# uINS.net
KiCad netlist of a schematic drawn in Altium Designer
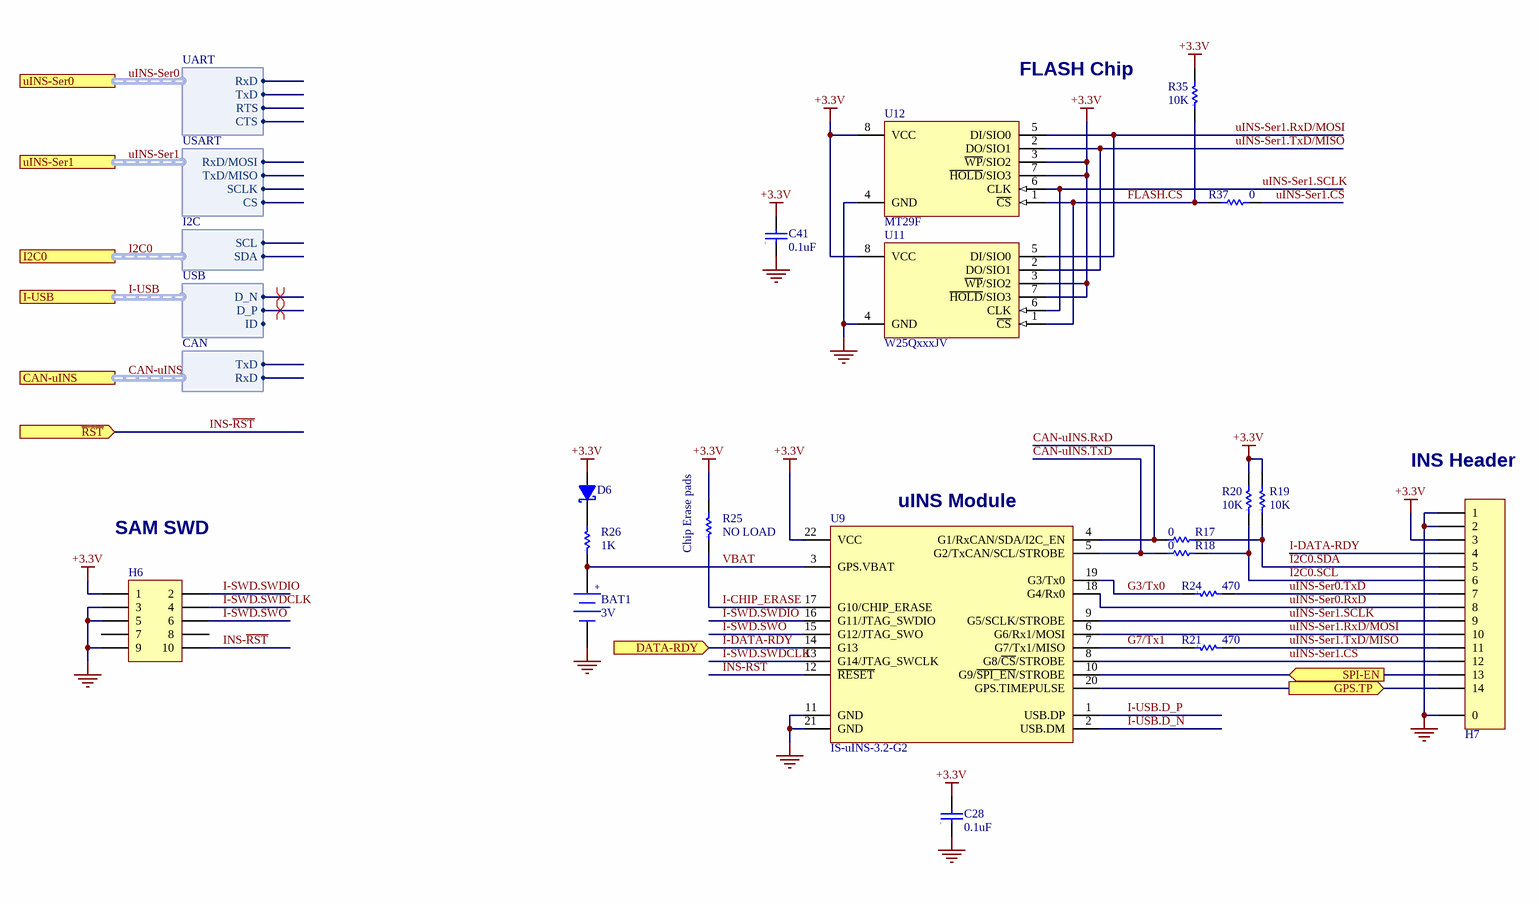
[diagram p0: uINS.SchDoc]

(export (version "E")
  (design (tool "Eeschema 10.0.6"))
  (components
    (comp (ref "BAT1")
      (value "Battery")
      (footprint "ML614S")
      (description "BATTERY LITH 3V RECHARGE SMD")
      (fields
        (field (name "MANUFACTURER") "Seiko")
        (field (name "MANUFACTURER PART NUMBER") "MS621T-FL11E")
        (field (name "VOLTAGE RATING") "3V")
      )
      (libsource (lib "General") (part "Battery"))
    )
    (comp (ref "C28")
      (value "0.1uF")
      (footprint "0402")
      (description "CAP CER .10UF 50V X7R 10% 0402")
      (fields
        (field (name "MANUFACTURER") "TDK Corporation")
        (field (name "MANUFACTURER PART NUMBER") "C1005X7R1H104K")
        (field (name "PUBLISHER") "Altium Limited")
      )
      (libsource (lib "General") (part "Cap"))
    )
    (comp (ref "C41")
      (value "0.1uF")
      (footprint "0402")
      (description "CAP CER .10UF 50V X7R 10% 0402")
      (fields
        (field (name "MANUFACTURER") "TDK Corporation")
        (field (name "MANUFACTURER PART NUMBER") "C1005X7R1H104K")
        (field (name "PUBLISHER") "Altium Limited")
      )
      (libsource (lib "General") (part "Cap"))
    )
    (comp (ref "D6")
      (value "Diode - Schottky")
      (footprint "D0603B")
      (description "DIODE SCHOTTKY 30V 2A 0603")
      (fields
        (field (name "MANUFACTURER") "Vishay")
        (field (name "MANUFACTURER PART NUMBER") "VSKY20301608-G4-08")
      )
      (libsource (lib "General") (part "Diode - Schottky"))
    )
    (comp (ref "H6")
      (value "Hdr - 5x2pin")
      (footprint "FTSH-105-01-L-DV-K-A-P")
      (description "CONN HEADER 10POS DUAL .05\" SMD")
      (fields
        (field (name "MANUFACTURER") "Samtec")
        (field (name "MANUFACTURER PART NUMBER") "FTSH-105-01-L-DV-K-A-P")
      )
      (libsource (lib "Connectors") (part "Hdr - 5x2pin"))
    )
    (comp (ref "H7")
      (value "Hdr - 14pin - mount")
      (footprint "SM14B-GHS-TB(LF)(SN)")
      (description "CONN HEADER GH SIDE 14POS 1.25MM")
      (fields
        (field (name "MANUFACTURER") "JST")
        (field (name "MANUFACTURER PART NUMBER") "SM14B-GHS-TB(LF)(SN)")
      )
      (libsource (lib "Connectors") (part "Hdr - 14pin - mount"))
    )
    (comp (ref "R17")
      (value "0")
      (footprint "R0402")
      (description "RES SMD 0 OHM JUMPER 1/16W 0402")
      (fields
        (field (name "MANUFACTURER") "Yageo")
        (field (name "MANUFACTURER PART NUMBER") "RC0402JR-070RL")
      )
      (libsource (lib "General") (part "Res"))
    )
    (comp (ref "R18")
      (value "0")
      (footprint "R0402")
      (description "RES SMD 0 OHM JUMPER 1/16W 0402")
      (fields
        (field (name "MANUFACTURER") "Yageo")
        (field (name "MANUFACTURER PART NUMBER") "RC0402JR-070RL")
      )
      (libsource (lib "General") (part "Res"))
    )
    (comp (ref "R19")
      (value "10K")
      (footprint "R0402")
      (description "RES 10K OHM 1/16W 1% 0402 SMD")
      (fields
        (field (name "MANUFACTURER") "Panasonic")
        (field (name "MANUFACTURER PART NUMBER") "ERJ-2RKF1002X")
      )
      (libsource (lib "") (part "Res_1"))
    )
    (comp (ref "R20")
      (value "10K")
      (footprint "R0402")
      (description "RES 10K OHM 1/16W 1% 0402 SMD")
      (fields
        (field (name "MANUFACTURER") "Panasonic")
        (field (name "MANUFACTURER PART NUMBER") "ERJ-2RKF1002X")
      )
      (libsource (lib "") (part "Res_1"))
    )
    (comp (ref "R21")
      (value "470")
      (footprint "R0402")
      (description "RES 470 OHM 1/16W 1% 0402 SMD")
      (fields
        (field (name "MANUFACTURER") "Vishay Dale")
        (field (name "MANUFACTURER PART NUMBER") "CRCW0402470RFKED")
      )
      (libsource (lib "") (part "Res_2"))
    )
    (comp (ref "R24")
      (value "470")
      (footprint "R0402")
      (description "RES 470 OHM 1/16W 1% 0402 SMD")
      (fields
        (field (name "MANUFACTURER") "Vishay Dale")
        (field (name "MANUFACTURER PART NUMBER") "CRCW0402470RFKED")
      )
      (libsource (lib "") (part "Res_2"))
    )
    (comp (ref "R25")
      (value "NO LOAD")
      (footprint "R0402")
      (description "RES 1.00K OHM 1/16W 1% 0402 SMD")
      (fields (field (name "Comment") "Res"))
      (libsource (lib "") (part "Res_1"))
    )
    (comp (ref "R26")
      (value "1K")
      (footprint "R0402")
      (description "RES 1.00K OHM 1/16W 1% 0402 SMD")
      (fields
        (field (name "MANUFACTURER") "Yageo")
        (field (name "MANUFACTURER PART NUMBER") "RC0402FR-071KL")
      )
      (libsource (lib "") (part "Res_1"))
    )
    (comp (ref "R35")
      (value "10K")
      (footprint "R0402")
      (description "RES 10K OHM 1/16W 1% 0402 SMD")
      (fields
        (field (name "MANUFACTURER") "Panasonic")
        (field (name "MANUFACTURER PART NUMBER") "ERJ-2RKF1002X")
      )
      (libsource (lib "") (part "Res_1"))
    )
    (comp (ref "R37")
      (value "0")
      (footprint "R0402")
      (description "RES SMD 0 OHM JUMPER 1/16W 0402")
      (fields
        (field (name "MANUFACTURER") "Yageo")
        (field (name "MANUFACTURER PART NUMBER") "RC0402JR-070RL")
      )
      (libsource (lib "General") (part "Res"))
    )
    (comp (ref "U9")
      (value "uINS")
      (footprint "IS-uINS-3.2_no_paste")
      (description "Inertial Sense uINS")
      (fields
        (field (name "MANUFACTURER") "Inertial Sense")
        (field (name "MANUFACTURER PART NUMBER") "IS-uINS-3.2-G2")
      )
      (libsource (lib "InertialSense") (part "IS-uINS-3.2"))
    )
    (comp (ref "U11")
      (value "W25QxxxJV")
      (footprint "SOIC127P790X216-8N")
      (description "IC FLASH 128M SPI 133MHZ 8SOIC")
      (fields
        (field (name "MANUFACTURER") "Winbond")
        (field (name "MANUFACTURER PART NUMBER") "W25Q128JVSIQTR")
      )
      (libsource (lib "ICs") (part "W25Q128JV"))
    )
    (comp (ref "U12")
      (value "MT29F")
      (footprint "DFN800X600X65-8N")
      (description "IC FLASH 1G/2G SPI 8UPDFN")
      (fields
        (field (name "MANUFACTURER") "Micron Technology")
        (field (name "MANUFACTURER PART NUMBER") "MT29F2G01ABAGDWB-IT:GTR")
      )
      (libsource (lib "ICs") (part "MT29F"))
    )
  )
  (nets
    (net (code "6") (name "+3.3V") (class "Default")
      (node (ref "C28") (pin "2") (pinfunction "2_2") (pintype "passive"))
      (node (ref "C41") (pin "2") (pinfunction "2_2") (pintype "passive"))
      (node (ref "D6") (pin "A") (pinfunction "A_A") (pintype "passive"))
      (node (ref "H6") (pin "1") (pinfunction "1_1") (pintype "passive"))
      (node (ref "H7") (pin "3") (pinfunction "3_3") (pintype "passive"))
      (node (ref "R19") (pin "2") (pinfunction "2_2") (pintype "passive"))
      (node (ref "R20") (pin "2") (pinfunction "2_2") (pintype "passive"))
      (node (ref "R25") (pin "2") (pinfunction "2_2") (pintype "passive"))
      (node (ref "R35") (pin "2") (pinfunction "2_2") (pintype "passive"))
      (node (ref "U11") (pin "3") (pinfunction "~{WP}/SIO2_3") (pintype "passive"))
      (node (ref "U11") (pin "7") (pinfunction "~{HOLD}/SIO3_7") (pintype "passive"))
      (node (ref "U11") (pin "8") (pinfunction "VCC_8") (pintype "power_in"))
      (node (ref "U12") (pin "3") (pinfunction "~{WP}/SIO2_3") (pintype "passive"))
      (node (ref "U12") (pin "7") (pinfunction "~{HOLD}/SIO3_7") (pintype "passive"))
      (node (ref "U12") (pin "8") (pinfunction "VCC_8") (pintype "power_in"))
      (node (ref "U9") (pin "22") (pinfunction "VCC_22") (pintype "power_in"))
    )
    (net (code "7") (name "/CAN-uINS.RxD") (class "Default")
      (node (ref "R17") (pin "1") (pinfunction "1_1") (pintype "passive"))
      (node (ref "U9") (pin "4") (pinfunction "G1/RxCAN/SDA/I2C_EN_4") (pintype "passive"))
    )
    (net (code "8") (name "/CAN-uINS.TxD") (class "Default")
      (node (ref "R18") (pin "1") (pinfunction "1_1") (pintype "passive"))
      (node (ref "U9") (pin "5") (pinfunction "G2/TxCAN/SCL/STROBE_5") (pintype "passive"))
    )
    (net (code "10") (name "/FLASH.CS") (class "Default")
      (node (ref "R35") (pin "1") (pinfunction "1_1") (pintype "passive"))
      (node (ref "R37") (pin "1") (pinfunction "1_1") (pintype "passive"))
      (node (ref "U11") (pin "1") (pinfunction "CS_1") (pintype "input"))
      (node (ref "U12") (pin "1") (pinfunction "CS_1") (pintype "input"))
    )
    (net (code "11") (name "/G3{slash}Tx0") (class "Default")
      (node (ref "R24") (pin "1") (pinfunction "1_1") (pintype "passive"))
      (node (ref "U9") (pin "19") (pinfunction "G3/Tx0_19") (pintype "passive"))
    )
    (net (code "12") (name "/G7{slash}Tx1") (class "Default")
      (node (ref "R21") (pin "1") (pinfunction "1_1") (pintype "passive"))
      (node (ref "U9") (pin "7") (pinfunction "G7/Tx1/MISO_7") (pintype "passive"))
    )
    (net (code "13") (name "/GPS.TP") (class "Default")
      (node (ref "H7") (pin "14") (pinfunction "14_14") (pintype "passive"))
      (node (ref "U9") (pin "20") (pinfunction "GPS.TIMEPULSE_20") (pintype "passive"))
    )
    (net (code "14") (name "/I-CHIP_ERASE") (class "Default")
      (node (ref "R25") (pin "1") (pinfunction "1_1") (pintype "passive"))
      (node (ref "U9") (pin "17") (pinfunction "G10/CHIP_ERASE_17") (pintype "passive"))
    )
    (net (code "15") (name "/I-DATA-RDY") (class "Default")
      (node (ref "H7") (pin "4") (pinfunction "4_4") (pintype "passive"))
      (node (ref "U9") (pin "14") (pinfunction "G13_14") (pintype "passive"))
    )
    (net (code "16") (name "/I-SWD.SWDCLK") (class "Default")
      (node (ref "H6") (pin "4") (pinfunction "4_4") (pintype "passive"))
      (node (ref "U9") (pin "13") (pinfunction "G14/JTAG_SWCLK_13") (pintype "passive"))
    )
    (net (code "17") (name "/I-SWD.SWDIO") (class "Default")
      (node (ref "H6") (pin "2") (pinfunction "2_2") (pintype "passive"))
      (node (ref "U9") (pin "16") (pinfunction "G11/JTAG_SWDIO_16") (pintype "passive"))
    )
    (net (code "18") (name "/I-SWD.SWO") (class "Default")
      (node (ref "H6") (pin "6") (pinfunction "6_6") (pintype "passive"))
      (node (ref "U9") (pin "15") (pinfunction "G12/JTAG_SWO_15") (pintype "passive"))
    )
    (net (code "19") (name "/I-USB.D_N") (class "Default")
      (node (ref "U9") (pin "2") (pinfunction "USB.DM_2") (pintype "passive"))
    )
    (net (code "20") (name "/I-USB.D_P") (class "Default")
      (node (ref "U9") (pin "1") (pinfunction "USB.DP_1") (pintype "passive"))
    )
    (net (code "22") (name "/I2C0.SCL") (class "Default")
      (node (ref "H7") (pin "6") (pinfunction "6_6") (pintype "passive"))
      (node (ref "R18") (pin "2") (pinfunction "2_2") (pintype "passive"))
      (node (ref "R20") (pin "1") (pinfunction "1_1") (pintype "passive"))
    )
    (net (code "23") (name "/I2C0.SDA") (class "Default")
      (node (ref "H7") (pin "5") (pinfunction "5_5") (pintype "passive"))
      (node (ref "R17") (pin "2") (pinfunction "2_2") (pintype "passive"))
      (node (ref "R19") (pin "1") (pinfunction "1_1") (pintype "passive"))
    )
    (net (code "25") (name "/INS-~{RST}") (class "Default")
      (node (ref "H6") (pin "10") (pinfunction "10_10") (pintype "passive"))
      (node (ref "U9") (pin "12") (pinfunction "~{RESET}_12") (pintype "passive"))
    )
    (net (code "26") (name "/SPI-EN") (class "Default")
      (node (ref "H7") (pin "13") (pinfunction "13_13") (pintype "passive"))
      (node (ref "U9") (pin "10") (pinfunction "G9/~{SPI_EN}/STROBE_10") (pintype "passive"))
    )
    (net (code "27") (name "/VBAT") (class "Default")
      (node (ref "BAT1") (pin "+") (pinfunction "+_+") (pintype "passive"))
      (node (ref "R26") (pin "1") (pinfunction "1_1") (pintype "passive"))
      (node (ref "U9") (pin "3") (pinfunction "GPS.VBAT_3") (pintype "passive"))
    )
    (net (code "28") (name "/uINS-Ser0.RxD") (class "Default")
      (node (ref "H7") (pin "8") (pinfunction "8_8") (pintype "passive"))
      (node (ref "U9") (pin "18") (pinfunction "G4/Rx0_18") (pintype "passive"))
    )
    (net (code "29") (name "/uINS-Ser0.TxD") (class "Default")
      (node (ref "H7") (pin "7") (pinfunction "7_7") (pintype "passive"))
      (node (ref "R24") (pin "2") (pinfunction "2_2") (pintype "passive"))
    )
    (net (code "31") (name "/uINS-Ser1.CS") (class "Default")
      (node (ref "H7") (pin "12") (pinfunction "12_12") (pintype "passive"))
      (node (ref "R37") (pin "2") (pinfunction "2_2") (pintype "passive"))
      (node (ref "U9") (pin "8") (pinfunction "G8/~{CS}/STROBE_8") (pintype "passive"))
    )
    (net (code "32") (name "/uINS-Ser1.RxD{slash}MOSI") (class "Default")
      (node (ref "H7") (pin "10") (pinfunction "10_10") (pintype "passive"))
      (node (ref "U11") (pin "5") (pinfunction "DI/SIO0_5") (pintype "passive"))
      (node (ref "U12") (pin "5") (pinfunction "DI/SIO0_5") (pintype "passive"))
      (node (ref "U9") (pin "6") (pinfunction "G6/Rx1/MOSI_6") (pintype "passive"))
    )
    (net (code "33") (name "/uINS-Ser1.SCLK") (class "Default")
      (node (ref "H7") (pin "9") (pinfunction "9_9") (pintype "passive"))
      (node (ref "U11") (pin "6") (pinfunction "CLK_6") (pintype "input"))
      (node (ref "U12") (pin "6") (pinfunction "CLK_6") (pintype "input"))
      (node (ref "U9") (pin "9") (pinfunction "G5/SCLK/STROBE_9") (pintype "passive"))
    )
    (net (code "34") (name "/uINS-Ser1.TxD{slash}MISO") (class "Default")
      (node (ref "H7") (pin "11") (pinfunction "11_11") (pintype "passive"))
      (node (ref "R21") (pin "2") (pinfunction "2_2") (pintype "passive"))
      (node (ref "U11") (pin "2") (pinfunction "DO/SIO1_2") (pintype "passive"))
      (node (ref "U12") (pin "2") (pinfunction "DO/SIO1_2") (pintype "passive"))
    )
    (net (code "36") (name "GND") (class "Default")
      (node (ref "BAT1") (pin "-") (pinfunction "-_-") (pintype "passive"))
      (node (ref "C28") (pin "1") (pinfunction "1_1") (pintype "passive"))
      (node (ref "C41") (pin "1") (pinfunction "1_1") (pintype "passive"))
      (node (ref "H6") (pin "3") (pinfunction "3_3") (pintype "passive"))
      (node (ref "H6") (pin "5") (pinfunction "5_5") (pintype "passive"))
      (node (ref "H6") (pin "9") (pinfunction "9_9") (pintype "passive"))
      (node (ref "H7") (pin "0") (pinfunction "0_0") (pintype "passive"))
      (node (ref "H7") (pin "1") (pinfunction "1_1") (pintype "passive"))
      (node (ref "H7") (pin "2") (pinfunction "2_2") (pintype "passive"))
      (node (ref "U11") (pin "4") (pinfunction "GND_4") (pintype "power_in"))
      (node (ref "U12") (pin "4") (pinfunction "GND_4") (pintype "power_in"))
      (node (ref "U9") (pin "11") (pinfunction "GND_11") (pintype "power_in"))
      (node (ref "U9") (pin "21") (pinfunction "GND_21") (pintype "power_in"))
    )
    (net (code "37") (name "Net-(D6-PadC)") (class "Default")
      (node (ref "D6") (pin "C") (pinfunction "C_C") (pintype "passive"))
      (node (ref "R26") (pin "2") (pinfunction "2_2") (pintype "passive"))
    )
    (net (code "38") (name "unconnected-(H6-Pad7)") (class "Default")
      (node (ref "H6") (pin "7") (pinfunction "7_7") (pintype "passive"))
    )
    (net (code "39") (name "unconnected-(H6-Pad8)") (class "Default")
      (node (ref "H6") (pin "8") (pinfunction "8_8") (pintype "passive"))
    )
  )
)
